# GoPro_Actuator_LED.net
KiCad netlist of a schematic drawn in Altium Designer
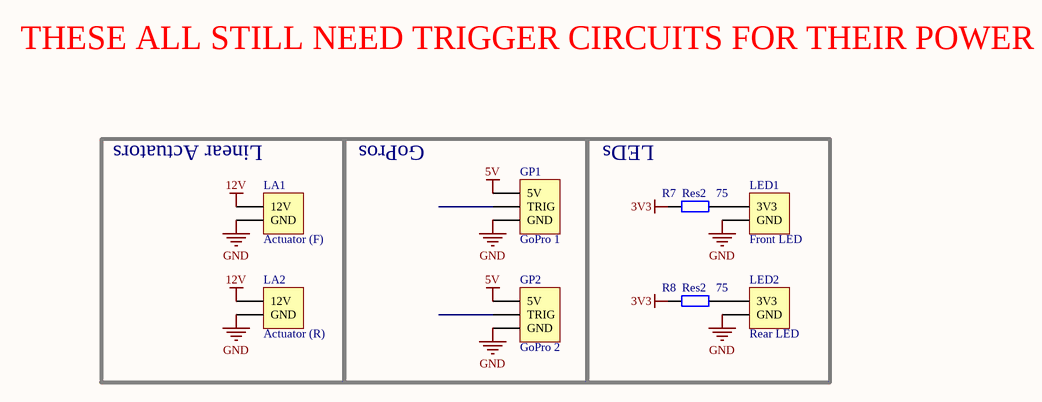
[diagram p0: GoPro_Actuator_LED.SchDoc]

(export (version "E")
  (design (tool "Eeschema 10.0.6"))
  (components
    (comp (ref "GP1")
      (value "GoPro 1")
      (footprint "HDR1X3")
      (description "Header, 3-Pin")
      (fields (field (name "PUBLISHER") "Altium Limited"))
      (libsource (lib "Miscellaneous Connectors") (part "Header 3"))
    )
    (comp (ref "GP2")
      (value "GoPro 2")
      (footprint "HDR1X3")
      (description "Header, 3-Pin")
      (fields (field (name "PUBLISHER") "Altium Limited"))
      (libsource (lib "Miscellaneous Connectors") (part "Header 3"))
    )
    (comp (ref "LA1")
      (value "Actuator (F)")
      (footprint "HDR1X2")
      (description "Header, 2-Pin")
      (fields (field (name "PUBLISHER") "Altium Limited"))
      (libsource (lib "Miscellaneous Connectors") (part "Header 2"))
    )
    (comp (ref "LA2")
      (value "Actuator (R)")
      (footprint "HDR1X2")
      (description "Header, 2-Pin")
      (fields (field (name "PUBLISHER") "Altium Limited"))
      (libsource (lib "Miscellaneous Connectors") (part "Header 2"))
    )
    (comp (ref "LED1")
      (value "Front LED")
      (footprint "HDR1X2")
      (description "Header, 2-Pin")
      (fields (field (name "PUBLISHER") "Altium Limited"))
      (libsource (lib "Miscellaneous Connectors") (part "Header 2"))
    )
    (comp (ref "LED2")
      (value "Rear LED")
      (footprint "HDR1X2")
      (description "Header, 2-Pin")
      (fields (field (name "PUBLISHER") "Altium Limited"))
      (libsource (lib "Miscellaneous Connectors") (part "Header 2"))
    )
    (comp (ref "R7")
      (value "Res2")
      (footprint "AXIAL-0.4")
      (description "Resistor")
      (fields (field (name "ALTIUM_VALUE") "75") (field (name "PUBLISHER") "Altium Limited"))
      (libsource (lib "Miscellaneous Devices") (part "Res2"))
    )
    (comp (ref "R8")
      (value "Res2")
      (footprint "AXIAL-0.4")
      (description "Resistor")
      (fields (field (name "ALTIUM_VALUE") "75") (field (name "PUBLISHER") "Altium Limited"))
      (libsource (lib "Miscellaneous Devices") (part "Res2"))
    )
  )
  (nets
    (net (code "1") (name "3V3") (class "Default")
      (node (ref "R7") (pin "2") (pinfunction "2_2") (pintype "passive"))
      (node (ref "R8") (pin "2") (pinfunction "2_2") (pintype "passive"))
    )
    (net (code "2") (name "5V") (class "Default")
      (node (ref "GP1") (pin "1") (pinfunction "5V_1") (pintype "passive"))
      (node (ref "GP2") (pin "1") (pinfunction "5V_1") (pintype "passive"))
    )
    (net (code "3") (name "12V") (class "Default")
      (node (ref "LA1") (pin "1") (pinfunction "12V_1") (pintype "passive"))
      (node (ref "LA2") (pin "1") (pinfunction "12V_1") (pintype "passive"))
    )
    (net (code "4") (name "GND") (class "Default")
      (node (ref "GP1") (pin "3") (pinfunction "GND_3") (pintype "passive"))
      (node (ref "GP2") (pin "3") (pinfunction "GND_3") (pintype "passive"))
      (node (ref "LA1") (pin "2") (pinfunction "GND_2") (pintype "passive"))
      (node (ref "LA2") (pin "2") (pinfunction "GND_2") (pintype "passive"))
      (node (ref "LED1") (pin "2") (pinfunction "GND_2") (pintype "passive"))
      (node (ref "LED2") (pin "2") (pinfunction "GND_2") (pintype "passive"))
    )
    (net (code "5") (name "Net-(LED1-12V)") (class "Default")
      (node (ref "LED1") (pin "1") (pinfunction "12V_1") (pintype "passive"))
      (node (ref "R7") (pin "1") (pinfunction "1_1") (pintype "passive"))
    )
    (net (code "6") (name "Net-(LED2-12V)") (class "Default")
      (node (ref "LED2") (pin "1") (pinfunction "12V_1") (pintype "passive"))
      (node (ref "R8") (pin "1") (pinfunction "1_1") (pintype "passive"))
    )
    (net (code "7") (name "unconnected-(GP1-TRIG-Pad2)") (class "Default")
      (node (ref "GP1") (pin "2") (pinfunction "TRIG_2") (pintype "passive"))
    )
    (net (code "8") (name "unconnected-(GP2-TRIG-Pad2)") (class "Default")
      (node (ref "GP2") (pin "2") (pinfunction "TRIG_2") (pintype "passive"))
    )
  )
)
